# OpAmpSupply.net
KiCad netlist of a schematic drawn in Altium Designer
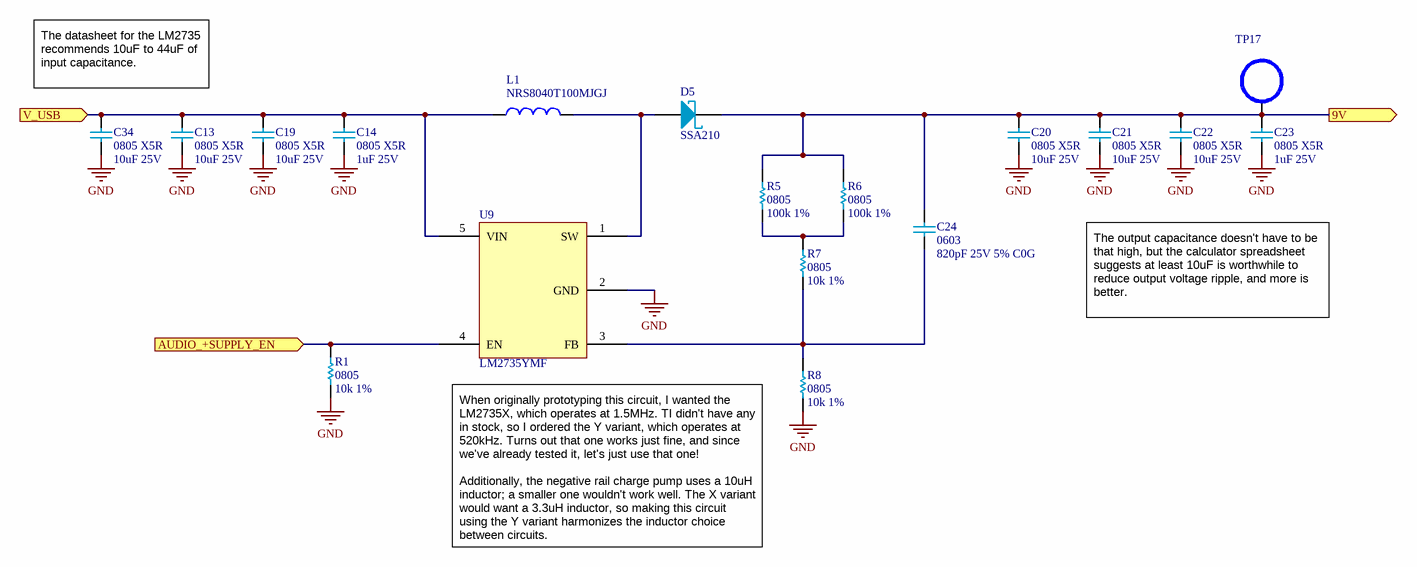
[diagram p0: OpAmpSupply.SchDoc]

(export (version "E")
  (design (tool "Eeschema 10.0.6"))
  (components
    (comp (ref "C13")
      (value "0805 X5R")
      (footprint "0805 - TALL")
      (description "0805, X5R or better")
      (fields (field (name "ALTIUM_VALUE") "10uF 25V"))
      (libsource (lib "Chip_Passives") (part "Cap 10uF 25V"))
    )
    (comp (ref "C14")
      (value "0805 X5R")
      (footprint "0805 - TALL")
      (description "0805, X5R or better")
      (fields (field (name "ALTIUM_VALUE") "1uF 25V"))
      (libsource (lib "Chip_Passives") (part "Cap 1uF 25V"))
    )
    (comp (ref "C19")
      (value "0805 X5R")
      (footprint "0805 - TALL")
      (description "0805, X5R or better")
      (fields (field (name "ALTIUM_VALUE") "10uF 25V"))
      (libsource (lib "Chip_Passives") (part "Cap 10uF 25V"))
    )
    (comp (ref "C20")
      (value "0805 X5R")
      (footprint "0805 - TALL")
      (description "0805, X5R or better")
      (fields (field (name "ALTIUM_VALUE") "10uF 25V"))
      (libsource (lib "Chip_Passives") (part "Cap 10uF 25V"))
    )
    (comp (ref "C21")
      (value "0805 X5R")
      (footprint "0805 - TALL")
      (description "0805, X5R or better")
      (fields (field (name "ALTIUM_VALUE") "10uF 25V"))
      (libsource (lib "Chip_Passives") (part "Cap 10uF 25V"))
    )
    (comp (ref "C22")
      (value "0805 X5R")
      (footprint "0805 - TALL")
      (description "0805, X5R or better")
      (fields (field (name "ALTIUM_VALUE") "10uF 25V"))
      (libsource (lib "Chip_Passives") (part "Cap 10uF 25V"))
    )
    (comp (ref "C23")
      (value "0805 X5R")
      (footprint "0805 - TALL")
      (description "0805, X5R or better")
      (fields (field (name "ALTIUM_VALUE") "1uF 25V"))
      (libsource (lib "Chip_Passives") (part "Cap 1uF 25V"))
    )
    (comp (ref "C24")
      (value "0603")
      (footprint "0603")
      (description "0603, 5% C0G or better")
      (fields (field (name "ALTIUM_VALUE") "820pF 25V 5% C0G"))
      (libsource (lib "Chip_Passives") (part "Cap 820pF 25V"))
    )
    (comp (ref "C34")
      (value "0805 X5R")
      (footprint "0805 - TALL")
      (description "0805, X5R or better")
      (fields (field (name "ALTIUM_VALUE") "10uF 25V"))
      (libsource (lib "Chip_Passives") (part "Cap 10uF 25V"))
    )
    (comp (ref "D5")
      (value "SSA210")
      (footprint "SSA210 - DO-214AC")
      (description "100V 2A Shottky Diode (Rectifier)")
      (libsource (lib "Diodes") (part "SSA210"))
    )
    (comp (ref "L1")
      (value "NRS8040T100MJGJ")
      (footprint "NRS8040T100MJGJ")
      (description "FIXED IND 10UH 3.1A 44.2MOHM SMD")
      (libsource (lib "Inductors") (part "NRS8040T100MJGJ"))
    )
    (comp (ref "R1")
      (value "0805")
      (footprint "0805")
      (description "Chip resistor")
      (fields (field (name "ALTIUM_VALUE") "10k 1%"))
      (libsource (lib "Chip_Passives") (part "Res 10k 1% 0805"))
    )
    (comp (ref "R5")
      (value "0805")
      (footprint "0805")
      (description "Chip resistor")
      (fields (field (name "ALTIUM_VALUE") "100k 1%"))
      (libsource (lib "Chip_Passives") (part "Res 100k 1% 0805"))
    )
    (comp (ref "R6")
      (value "0805")
      (footprint "0805")
      (description "Chip resistor")
      (fields (field (name "ALTIUM_VALUE") "100k 1%"))
      (libsource (lib "Chip_Passives") (part "Res 100k 1% 0805"))
    )
    (comp (ref "R7")
      (value "0805")
      (footprint "0805")
      (description "Chip resistor")
      (fields (field (name "ALTIUM_VALUE") "10k 1%"))
      (libsource (lib "Chip_Passives") (part "Res 10k 1% 0805"))
    )
    (comp (ref "R8")
      (value "0805")
      (footprint "0805")
      (description "Chip resistor")
      (fields (field (name "ALTIUM_VALUE") "10k 1%"))
      (libsource (lib "Chip_Passives") (part "Res 10k 1% 0805"))
    )
    (comp (ref "TP17")
      (value "TestPointHook")
      (footprint "S2751-46R")
      (description "Test point, SMT ring (micro-hook compatible)")
      (libsource (lib "PCBFeatures") (part "TestPointHook"))
    )
    (comp (ref "U9")
      (value "LM2735YMF")
      (footprint "LM2735XMF - SOT95P280X145-5M")
      (description "LM2735 520-kHz Space-Efficient Boost and SEPIC DC/DC Regulator")
      (libsource (lib "PowerSupply") (part "LM2735YMF"))
    )
  )
  (nets
    (net (code "1") (name "/9V") (class "Default")
      (node (ref "C20") (pin "2") (pinfunction "2_2") (pintype "passive"))
      (node (ref "C21") (pin "2") (pinfunction "2_2") (pintype "passive"))
      (node (ref "C22") (pin "2") (pinfunction "2_2") (pintype "passive"))
      (node (ref "C23") (pin "2") (pinfunction "2_2") (pintype "passive"))
      (node (ref "C24") (pin "2") (pinfunction "2_2") (pintype "passive"))
      (node (ref "D5") (pin "1") (pinfunction "C_1") (pintype "passive"))
      (node (ref "R5") (pin "2") (pinfunction "2_2") (pintype "passive"))
      (node (ref "R6") (pin "2") (pinfunction "2_2") (pintype "passive"))
      (node (ref "TP17") (pin "1") (pinfunction "1_1") (pintype "passive"))
    )
    (net (code "2") (name "/AUDIO_+SUPPLY_EN") (class "Default")
      (node (ref "R1") (pin "2") (pinfunction "2_2") (pintype "passive"))
      (node (ref "U9") (pin "4") (pinfunction "EN_4") (pintype "passive"))
    )
    (net (code "3") (name "/V_USB") (class "Default")
      (node (ref "C13") (pin "2") (pinfunction "2_2") (pintype "passive"))
      (node (ref "C14") (pin "2") (pinfunction "2_2") (pintype "passive"))
      (node (ref "C19") (pin "2") (pinfunction "2_2") (pintype "passive"))
      (node (ref "C34") (pin "2") (pinfunction "2_2") (pintype "passive"))
      (node (ref "L1") (pin "1") (pinfunction "1_1") (pintype "passive"))
      (node (ref "U9") (pin "5") (pinfunction "VIN_5") (pintype "passive"))
    )
    (net (code "4") (name "GND") (class "Default")
      (node (ref "C13") (pin "1") (pinfunction "1_1") (pintype "passive"))
      (node (ref "C14") (pin "1") (pinfunction "1_1") (pintype "passive"))
      (node (ref "C19") (pin "1") (pinfunction "1_1") (pintype "passive"))
      (node (ref "C20") (pin "1") (pinfunction "1_1") (pintype "passive"))
      (node (ref "C21") (pin "1") (pinfunction "1_1") (pintype "passive"))
      (node (ref "C22") (pin "1") (pinfunction "1_1") (pintype "passive"))
      (node (ref "C23") (pin "1") (pinfunction "1_1") (pintype "passive"))
      (node (ref "C34") (pin "1") (pinfunction "1_1") (pintype "passive"))
      (node (ref "R1") (pin "1") (pinfunction "1_1") (pintype "passive"))
      (node (ref "R8") (pin "1") (pinfunction "1_1") (pintype "passive"))
      (node (ref "U9") (pin "2") (pinfunction "GND_2") (pintype "passive"))
    )
    (net (code "5") (name "Net-(R5-Pad1)") (class "Default")
      (node (ref "R5") (pin "1") (pinfunction "1_1") (pintype "passive"))
      (node (ref "R6") (pin "1") (pinfunction "1_1") (pintype "passive"))
      (node (ref "R7") (pin "2") (pinfunction "2_2") (pintype "passive"))
    )
    (net (code "6") (name "Net-(U9-FB)") (class "Default")
      (node (ref "C24") (pin "1") (pinfunction "1_1") (pintype "passive"))
      (node (ref "R7") (pin "1") (pinfunction "1_1") (pintype "passive"))
      (node (ref "R8") (pin "2") (pinfunction "2_2") (pintype "passive"))
      (node (ref "U9") (pin "3") (pinfunction "FB_3") (pintype "passive"))
    )
    (net (code "7") (name "Net-(U9-SW)") (class "Default")
      (node (ref "D5") (pin "2") (pinfunction "2_2") (pintype "passive"))
      (node (ref "L1") (pin "2") (pinfunction "2_2") (pintype "passive"))
      (node (ref "U9") (pin "1") (pinfunction "SW_1") (pintype "passive"))
    )
  )
)
